# Power_Supply_Input.net
KiCad netlist of a schematic drawn in Altium Designer
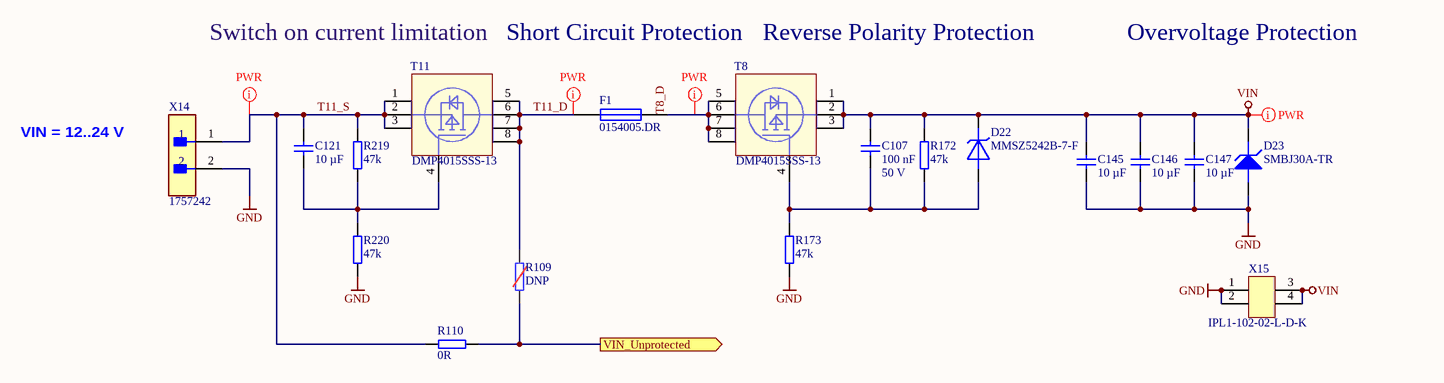
[diagram p0: Power_Supply_Input.SchDoc]

(export (version "E")
  (design (tool "Eeschema 10.0.6"))
  (components
    (comp (ref "C107")
      (value "100 nF")
      (footprint "C_0603_TE")
      (description "Generic capacitor")
      (fields
        (field (name "TOLERANCE") "10 %")
        (field (name "VOLTAGE") "50 V")
        (field (name "MANUFACTURER PART NUMBER") "UZgen_C_0603_100nF_50V_X7R")
        (field (name "CREATED FROM") "AGeiger")
      )
      (libsource (lib "user") (part "CAP-NP"))
    )
    (comp (ref "C121")
      (value "10 µF")
      (footprint "C_1206_TE")
      (description "Generic capacitor")
      (fields
        (field (name "TOLERANCE") "10 %")
        (field (name "MANUFACTURER PART NUMBER") "UZgen_C_1206_10uF_50V_X7R")
        (field (name "CREATED FROM") "MGeier")
      )
      (libsource (lib "user") (part "CAP-NP"))
    )
    (comp (ref "C145")
      (value "10 µF")
      (footprint "C_1206_TE")
      (description "Generic capacitor")
      (fields
        (field (name "TOLERANCE") "10 %")
        (field (name "MANUFACTURER PART NUMBER") "UZgen_C_1206_10uF_50V_X7R")
        (field (name "CREATED FROM") "MGeier")
      )
      (libsource (lib "user") (part "CAP-NP"))
    )
    (comp (ref "C146")
      (value "10 µF")
      (footprint "C_1206_TE")
      (description "Generic capacitor")
      (fields
        (field (name "TOLERANCE") "10 %")
        (field (name "MANUFACTURER PART NUMBER") "UZgen_C_1206_10uF_50V_X7R")
        (field (name "CREATED FROM") "MGeier")
      )
      (libsource (lib "user") (part "CAP-NP"))
    )
    (comp (ref "C147")
      (value "10 µF")
      (footprint "C_1206_TE")
      (description "Generic capacitor")
      (fields
        (field (name "TOLERANCE") "10 %")
        (field (name "MANUFACTURER PART NUMBER") "UZgen_C_1206_10uF_50V_X7R")
        (field (name "CREATED FROM") "MGeier")
      )
      (libsource (lib "user") (part "CAP-NP"))
    )
    (comp (ref "D22")
      (value "MMSZ5242B-7-F")
      (footprint "DIOM5226X240N")
      (description "Zener Diode, 12V, 500 mW")
      (fields
        (field (name "MANUFACTURER") "Diodes Incorporated")
        (field (name "POWER") "0.5W")
        (field (name "CREATED FROM") "MGremer")
      )
      (libsource (lib "user") (part "MMSZ5242B-7-F"))
    )
    (comp (ref "D23")
      (value "SMBJ30A-TR")
      (footprint "DIOM5436X244N")
      (description "TVS Diode 30V 600W SMB unidirectional / ESD suppressor")
      (fields
        (field (name "MANUFACTURER") "STMicroelectronics")
        (field (name "LCSC PART NUMBER") "C133663")
        (field (name "CREATED FROM") "PBaumann")
      )
      (libsource (lib "user") (part "TVS_Unidir_SMB"))
    )
    (comp (ref "F1")
      (value "0154005.DR")
      (footprint "Littlefuse_154")
      (description "Fuse OMNI BLOK 154")
      (fields
        (field (name "MANUFACTURER") "Littlefuse")
        (field (name "LCSC PART NUMBER") "C206916")
        (field (name "CREATED FROM") "MGremer")
      )
      (libsource (lib "user") (part "Fuse Littelfuse 154 Fuse"))
    )
    (comp (ref "R109")
      (value "DNP")
      (footprint "R_1206_TE-DNP")
      (description "Generic resistor (DNP)")
      (fields
        (field (name "MANUFACTURER PART NUMBER") "UZgen_R_1206_DNP")
        (field (name "MANUFACTURER") "UZgen")
        (field (name "CREATED FROM") "UZgenTool")
      )
      (libsource (lib "user") (part "RES-DNP"))
    )
    (comp (ref "R110")
      (value "0R")
      (footprint "R_1206_TE")
      (description "Generic resistor")
      (fields
        (field (name "MANUFACTURER PART NUMBER") "UZgen_R_1206_0R")
        (field (name "MANUFACTURER") "UZgen")
        (field (name "CREATED FROM") "UZgenTool")
      )
      (libsource (lib "user") (part "RES"))
    )
    (comp (ref "R172")
      (value "47k")
      (footprint "R_0603_TE")
      (description "Generic resistor")
      (fields
        (field (name "TOLERANCE") "1 %")
        (field (name "MANUFACTURER PART NUMBER") "UZgen_R_0603_47k")
        (field (name "CREATED FROM") "UZgenTool")
      )
      (libsource (lib "user") (part "RES"))
    )
    (comp (ref "R173")
      (value "47k")
      (footprint "R_0603_TE")
      (description "Generic resistor")
      (fields
        (field (name "TOLERANCE") "1 %")
        (field (name "MANUFACTURER PART NUMBER") "UZgen_R_0603_47k")
        (field (name "CREATED FROM") "UZgenTool")
      )
      (libsource (lib "user") (part "RES"))
    )
    (comp (ref "R219")
      (value "47k")
      (footprint "R_0603_TE")
      (description "Generic resistor")
      (fields
        (field (name "TOLERANCE") "1 %")
        (field (name "MANUFACTURER PART NUMBER") "UZgen_R_0603_47k")
        (field (name "CREATED FROM") "UZgenTool")
      )
      (libsource (lib "user") (part "RES"))
    )
    (comp (ref "R220")
      (value "47k")
      (footprint "R_0603_TE")
      (description "Generic resistor")
      (fields
        (field (name "TOLERANCE") "1 %")
        (field (name "MANUFACTURER PART NUMBER") "UZgen_R_0603_47k")
        (field (name "CREATED FROM") "UZgenTool")
      )
      (libsource (lib "user") (part "RES"))
    )
    (comp (ref "T8")
      (value "DMP4015SSS-13")
      (footprint "SOIC127P600X175-8N")
      (description "MOSFET MOSFET BVDSS: 41V-60 1V-60V SO-8 T&R 2.5K")
      (fields
        (field (name "MANUFACTURER") "Diodes Incorporated")
        (field (name "LCSC PART NUMBER") "C508210")
        (field (name "CREATED FROM") "FRosner")
      )
      (libsource (lib "user") (part "DMP4015"))
    )
    (comp (ref "T11")
      (value "DMP4015SSS-13")
      (footprint "SOIC127P600X175-8N")
      (description "MOSFET MOSFET BVDSS: 41V-60 1V-60V SO-8 T&R 2.5K")
      (fields
        (field (name "MANUFACTURER") "Diodes Incorporated")
        (field (name "LCSC PART NUMBER") "C508210")
        (field (name "CREATED FROM") "FRosner")
      )
      (libsource (lib "") (part "DMP4015_1"))
    )
    (comp (ref "X14")
      (value "1757242")
      (footprint "1757242")
      (description "Pluggable Terminal Blocks 2 Pos 5.08mm pitch Through Hole Header")
      (fields
        (field (name "MANUFACTURER") "Phoenix Contact")
        (field (name "LCSC PART NUMBER") "C90074")
        (field (name "CREATED FROM") "FRosner")
      )
      (libsource (lib "user") (part "1757242"))
    )
    (comp (ref "X15")
      (value "IPL1-102-02-L-D-K")
      (footprint "IPL1-102-02-L-D-K")
      (libsource (lib "TE") (part "CON-4-CUST"))
    )
  )
  (nets
    (net (code "1") (name "/T8_D") (class "Default")
      (node (ref "F1") (pin "2") (pinfunction "2_2") (pintype "passive"))
      (node (ref "T8") (pin "5") (pinfunction "DRAIN_5") (pintype "passive"))
      (node (ref "T8") (pin "6") (pinfunction "DRAIN_6") (pintype "passive"))
      (node (ref "T8") (pin "7") (pinfunction "DRAIN_7") (pintype "passive"))
      (node (ref "T8") (pin "8") (pinfunction "DRAIN_8") (pintype "passive"))
    )
    (net (code "2") (name "/T11_D") (class "Default")
      (node (ref "F1") (pin "1") (pinfunction "1_1") (pintype "passive"))
      (node (ref "R109") (pin "2") (pinfunction "2_2") (pintype "passive"))
      (node (ref "T11") (pin "5") (pinfunction "DRAIN_5") (pintype "passive"))
      (node (ref "T11") (pin "6") (pinfunction "DRAIN_6") (pintype "passive"))
      (node (ref "T11") (pin "7") (pinfunction "DRAIN_7") (pintype "passive"))
      (node (ref "T11") (pin "8") (pinfunction "DRAIN_8") (pintype "passive"))
    )
    (net (code "3") (name "/T11_S") (class "Default")
      (node (ref "C121") (pin "1") (pinfunction "1_1") (pintype "passive"))
      (node (ref "R110") (pin "1") (pinfunction "1_1") (pintype "passive"))
      (node (ref "R219") (pin "2") (pinfunction "2_2") (pintype "passive"))
      (node (ref "T11") (pin "1") (pinfunction "SOURCE_1") (pintype "passive"))
      (node (ref "T11") (pin "2") (pinfunction "SOURCE_2") (pintype "passive"))
      (node (ref "T11") (pin "3") (pinfunction "SOURCE_3") (pintype "passive"))
      (node (ref "X14") (pin "1") (pinfunction "1_1") (pintype "passive"))
    )
    (net (code "4") (name "/VIN_Unprotected") (class "Default")
      (node (ref "R109") (pin "1") (pinfunction "1_1") (pintype "passive"))
      (node (ref "R110") (pin "2") (pinfunction "2_2") (pintype "passive"))
    )
    (net (code "5") (name "GND") (class "Default")
      (node (ref "C145") (pin "1") (pinfunction "1_1") (pintype "passive"))
      (node (ref "C146") (pin "1") (pinfunction "1_1") (pintype "passive"))
      (node (ref "C147") (pin "1") (pinfunction "1_1") (pintype "passive"))
      (node (ref "D23") (pin "2") (pinfunction "ANODE_2") (pintype "passive"))
      (node (ref "R173") (pin "1") (pinfunction "1_1") (pintype "passive"))
      (node (ref "R220") (pin "1") (pinfunction "1_1") (pintype "passive"))
      (node (ref "X14") (pin "2") (pinfunction "2_2") (pintype "passive"))
      (node (ref "X15") (pin "1") (pinfunction "1_1") (pintype "passive"))
      (node (ref "X15") (pin "2") (pinfunction "2_2") (pintype "passive"))
    )
    (net (code "6") (name "Net-(D22-A)") (class "Default")
      (node (ref "C107") (pin "2") (pinfunction "2_2") (pintype "passive"))
      (node (ref "D22") (pin "1") (pinfunction "A_1") (pintype "passive"))
      (node (ref "R172") (pin "1") (pinfunction "1_1") (pintype "passive"))
      (node (ref "R173") (pin "2") (pinfunction "2_2") (pintype "passive"))
      (node (ref "T8") (pin "4") (pinfunction "GATE_4") (pintype "passive"))
    )
    (net (code "7") (name "Net-(T11-GATE)") (class "Default")
      (node (ref "C121") (pin "2") (pinfunction "2_2") (pintype "passive"))
      (node (ref "R219") (pin "1") (pinfunction "1_1") (pintype "passive"))
      (node (ref "R220") (pin "2") (pinfunction "2_2") (pintype "passive"))
      (node (ref "T11") (pin "4") (pinfunction "GATE_4") (pintype "passive"))
    )
    (net (code "8") (name "VIN") (class "Default")
      (node (ref "C107") (pin "1") (pinfunction "1_1") (pintype "passive"))
      (node (ref "C145") (pin "2") (pinfunction "2_2") (pintype "passive"))
      (node (ref "C146") (pin "2") (pinfunction "2_2") (pintype "passive"))
      (node (ref "C147") (pin "2") (pinfunction "2_2") (pintype "passive"))
      (node (ref "D22") (pin "2") (pinfunction "K_2") (pintype "passive"))
      (node (ref "D23") (pin "1") (pinfunction "KATHODE_1") (pintype "passive"))
      (node (ref "R172") (pin "2") (pinfunction "2_2") (pintype "passive"))
      (node (ref "T8") (pin "1") (pinfunction "SOURCE_1") (pintype "passive"))
      (node (ref "T8") (pin "2") (pinfunction "SOURCE_2") (pintype "passive"))
      (node (ref "T8") (pin "3") (pinfunction "SOURCE_3") (pintype "passive"))
      (node (ref "X15") (pin "3") (pinfunction "3_3") (pintype "passive"))
      (node (ref "X15") (pin "4") (pinfunction "4_4") (pintype "passive"))
    )
  )
)
